# PSFB_low_voltage_supply.net
KiCad netlist of a schematic drawn in Altium Designer
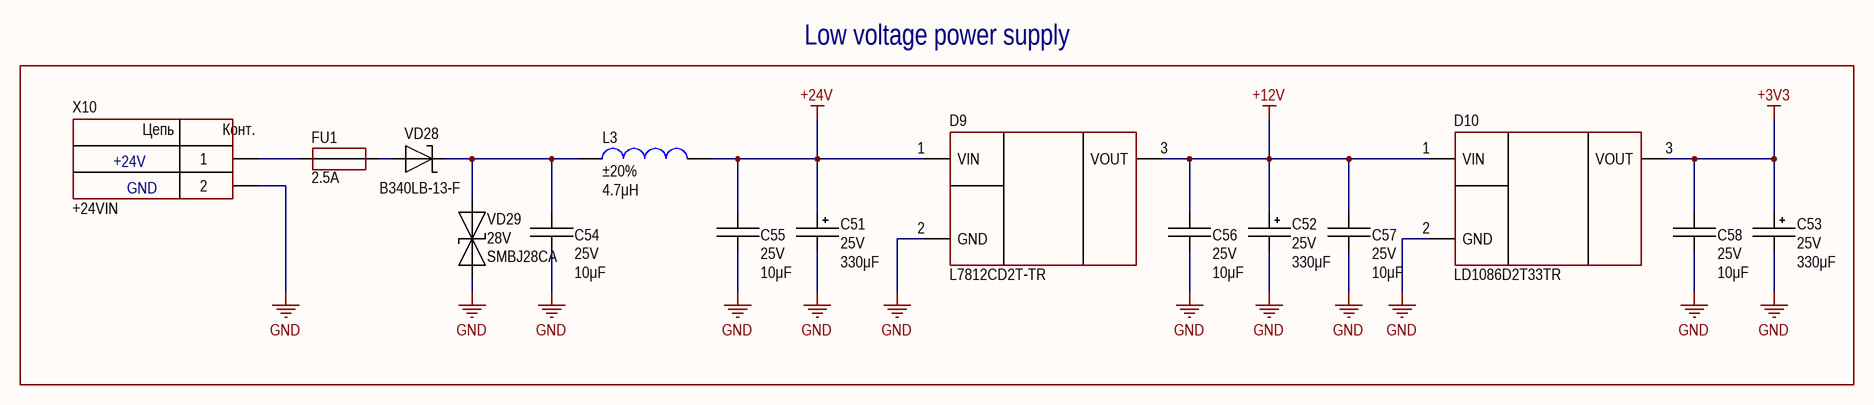
[diagram p0: PSFB_low_voltage_supply.SchDoc]

(export (version "E")
  (design (tool "Eeschema 10.0.6"))
  (components
    (comp (ref "C51")
      (value "330μF")
      (footprint "CAP: D8C3.5H12")
      (description "330µF 25V Aluminum - Polymer Capacitors Radial, Can 18mOhm 2000 Hrs @ 105°C")
      (fields
        (field (name "MANUFACTURER") "KEMET")
        (field (name "PARTNUMBER") "A750KS337M1EAAE018")
        (field (name "VOLTAGE") "25V")
      )
      (libsource (lib "capacitor") (part "Aluminium"))
    )
    (comp (ref "C52")
      (value "330μF")
      (footprint "CAP: D8C3.5H12")
      (description "330µF 25V Aluminum - Polymer Capacitors Radial, Can 18mOhm 2000 Hrs @ 105°C")
      (fields
        (field (name "MANUFACTURER") "KEMET")
        (field (name "PARTNUMBER") "A750KS337M1EAAE018")
        (field (name "VOLTAGE") "25V")
      )
      (libsource (lib "capacitor") (part "Aluminium"))
    )
    (comp (ref "C53")
      (value "330μF")
      (footprint "CAP: D8C3.5H12")
      (description "330µF 25V Aluminum - Polymer Capacitors Radial, Can 18mOhm 2000 Hrs @ 105°C")
      (fields
        (field (name "MANUFACTURER") "KEMET")
        (field (name "PARTNUMBER") "A750KS337M1EAAE018")
        (field (name "VOLTAGE") "25V")
      )
      (libsource (lib "capacitor") (part "Aluminium"))
    )
    (comp (ref "C54")
      (value "10μF")
      (footprint "CAP: 1206")
      (description "10µF ±10% 25V Ceramic Capacitor X7R 1206 (3216 Metric)")
      (fields
        (field (name "MANUFACTURER") "Yageo")
        (field (name "PARTNUMBER") "CC1206KKX7R8BB106")
        (field (name "VOLTAGE") "25V")
      )
      (libsource (lib "capacitor") (part "Ceramic_1206"))
    )
    (comp (ref "C55")
      (value "10μF")
      (footprint "CAP: 1206")
      (description "10µF ±10% 25V Ceramic Capacitor X7R 1206 (3216 Metric)")
      (fields
        (field (name "MANUFACTURER") "Yageo")
        (field (name "PARTNUMBER") "CC1206KKX7R8BB106")
        (field (name "VOLTAGE") "25V")
      )
      (libsource (lib "capacitor") (part "Ceramic_1206"))
    )
    (comp (ref "C56")
      (value "10μF")
      (footprint "CAP: 1206")
      (description "10µF ±10% 25V Ceramic Capacitor X7R 1206 (3216 Metric)")
      (fields
        (field (name "MANUFACTURER") "Yageo")
        (field (name "PARTNUMBER") "CC1206KKX7R8BB106")
        (field (name "VOLTAGE") "25V")
      )
      (libsource (lib "capacitor") (part "Ceramic_1206"))
    )
    (comp (ref "C57")
      (value "10μF")
      (footprint "CAP: 1206")
      (description "10µF ±10% 25V Ceramic Capacitor X7R 1206 (3216 Metric)")
      (fields
        (field (name "MANUFACTURER") "Yageo")
        (field (name "PARTNUMBER") "CC1206KKX7R8BB106")
        (field (name "VOLTAGE") "25V")
      )
      (libsource (lib "capacitor") (part "Ceramic_1206"))
    )
    (comp (ref "C58")
      (value "10μF")
      (footprint "CAP: 1206")
      (description "10µF ±10% 25V Ceramic Capacitor X7R 1206 (3216 Metric)")
      (fields
        (field (name "MANUFACTURER") "Yageo")
        (field (name "PARTNUMBER") "CC1206KKX7R8BB106")
        (field (name "VOLTAGE") "25V")
      )
      (libsource (lib "capacitor") (part "Ceramic_1206"))
    )
    (comp (ref "D9")
      (value "~")
      (footprint "D2PAK")
      (description "Linear Voltage Regulator IC Positive Fixed 1 Output  1.5A D2PAK")
      (fields
        (field (name "MANUFACTURER") "STMicroelectronics")
        (field (name "VALUEMANUFACTURERPARTNUMBER") "Linear voltage regulator, input 14...35V, 2V, output 12V, 1.5A, -40...+125°C, TO-220")
        (field (name "PARTNUMBER") "L7812CD2T-TR")
      )
      (libsource (lib "MyLib") (part "L7805ABV"))
    )
    (comp (ref "D10")
      (value "~")
      (footprint "D2PAK")
      (description "Linear Voltage Regulator IC Positive Fixed 1 Output  1.5A D2PAK")
      (fields
        (field (name "MANUFACTURER") "STMicroelectronics")
        (field (name "VALUEMANUFACTURERPARTNUMBER") "Linear voltage regulator, input 4.8...30V, 2V, output 3.3V, 1.5A, -40...+125°C, TO-220")
        (field (name "PARTNUMBER") "LD1086D2T33TR")
      )
      (libsource (lib "MyLib") (part "L7805ABV"))
    )
    (comp (ref "FU1")
      (value "~")
      (footprint "FUSE: 1206")
      (description "2.5A 125V AC 63V DC Fuse Board Mount (Cartridge Style Excluded) Surface Mount 1206 (3216 Metric)")
      (fields
        (field (name "MANUFACTURER") "Bel Fuse Inc.")
        (field (name "VALUEMANUFACTURERPARTNUMBER") "Electromechanics relay, 63V, 2.5A, 1206, ")
        (field (name "MAXCURRENT") "2.5A")
      )
      (libsource (lib "electromechanics") (part "Fuse"))
    )
    (comp (ref "L3")
      (value "4.7μH")
      (footprint "IND: SDR0403")
      (description "4.7µH Unshielded Wirewound Inductor 1.7A 94mOhm Max Nonstandard")
      (fields
        (field (name "MANUFACTURER") "Bourns")
        (field (name "PARTNUMBER") "SDR0403-4R7ML")
        (field (name "TOLERANCE") "±20%")
      )
      (libsource (lib "inductor") (part "Inductor_SDR0403"))
    )
    (comp (ref "VD28")
      (value "~")
      (footprint "DIODE: SMB")
      (description "Diode Schottky 40V 3A Surface Mount SMB")
      (fields
        (field (name "MANUFACTURER") "Diodes Incorporated")
        (field (name "VALUEMANUFACTURERPARTNUMBER") "Schottky diode, 40V, 3A, 0.45V, 100pF, SMB, -55...+150°C")
        (field (name "PARTNUMBER") "B340LB-13-F")
      )
      (libsource (lib "diode") (part "Schottky_single"))
    )
    (comp (ref "VD29")
      (value "~")
      (footprint "DIODE: SMB")
      (description "45.4V Clamp 13.3A Ipp Tvs Diode Surface Mount DO-214AA (SMBJ)")
      (fields
        (field (name "MANUFACTURER") "Diodes Incorporated")
        (field (name "VALUEMANUFACTURERPARTNUMBER") "TVS diode, 28V, 600W, , , SMB, -55...+150°C")
        (field (name "VOLTAGE") "28V")
        (field (name "PARTNUMBER") "SMBJ28CA")
      )
      (libsource (lib "diode") (part "TVS_single"))
    )
    (comp (ref "X10")
      (value "~")
      (footprint "CON: 6PCV-02-006")
      (description "2 Circuit 0.375\" (9.53mm) Barrier Block Connector, Screws")
      (fields
        (field (name "MANUFACTURER") "TE Connectivity")
        (field (name "VALUEMANUFACTURERPARTNUMBER") "Connector, 2pin, 9.53mm, 300VAC, 25A")
        (field (name "COMMENTTEXT") "+24VIN")
      )
      (libsource (lib "connector") (part "Connector_6PCV-02"))
    )
  )
  (nets
    (net (code "1") (name "+3V3") (class "Default")
      (node (ref "C53") (pin "1") (pinfunction "1_1") (pintype "passive"))
      (node (ref "C58") (pin "1") (pinfunction "1_1") (pintype "passive"))
      (node (ref "D10") (pin "3") (pinfunction "VOUT_3") (pintype "power_in"))
    )
    (net (code "2") (name "+12V") (class "Default")
      (node (ref "C52") (pin "1") (pinfunction "1_1") (pintype "passive"))
      (node (ref "C56") (pin "1") (pinfunction "1_1") (pintype "passive"))
      (node (ref "C57") (pin "1") (pinfunction "1_1") (pintype "passive"))
      (node (ref "D10") (pin "1") (pinfunction "VIN_1") (pintype "power_in"))
      (node (ref "D9") (pin "3") (pinfunction "VOUT_3") (pintype "power_in"))
    )
    (net (code "3") (name "+24V") (class "Default")
      (node (ref "C51") (pin "1") (pinfunction "1_1") (pintype "passive"))
      (node (ref "C55") (pin "1") (pinfunction "1_1") (pintype "passive"))
      (node (ref "D9") (pin "1") (pinfunction "VIN_1") (pintype "power_in"))
      (node (ref "L3") (pin "1") (pinfunction "1_1") (pintype "passive"))
    )
    (net (code "4") (name "GND") (class "Default")
      (node (ref "C51") (pin "2") (pinfunction "2_2") (pintype "passive"))
      (node (ref "C52") (pin "2") (pinfunction "2_2") (pintype "passive"))
      (node (ref "C53") (pin "2") (pinfunction "2_2") (pintype "passive"))
      (node (ref "C54") (pin "2") (pinfunction "2_2") (pintype "passive"))
      (node (ref "C55") (pin "2") (pinfunction "2_2") (pintype "passive"))
      (node (ref "C56") (pin "2") (pinfunction "2_2") (pintype "passive"))
      (node (ref "C57") (pin "2") (pinfunction "2_2") (pintype "passive"))
      (node (ref "C58") (pin "2") (pinfunction "2_2") (pintype "passive"))
      (node (ref "D10") (pin "2") (pinfunction "GND_2") (pintype "power_in"))
      (node (ref "D9") (pin "2") (pinfunction "GND_2") (pintype "power_in"))
      (node (ref "VD29") (pin "2") (pinfunction "C_2") (pintype "passive"))
      (node (ref "X10") (pin "2") (pinfunction "2_2") (pintype "passive"))
    )
    (net (code "5") (name "Net-(FU1-Pad1)") (class "Default")
      (node (ref "FU1") (pin "1") (pinfunction "1_1") (pintype "passive"))
      (node (ref "X10") (pin "1") (pinfunction "1_1") (pintype "passive"))
    )
    (net (code "6") (name "Net-(FU1-Pad2)") (class "Default")
      (node (ref "FU1") (pin "2") (pinfunction "2_2") (pintype "passive"))
      (node (ref "VD28") (pin "1") (pinfunction "1_1") (pintype "passive"))
    )
    (net (code "7") (name "Net-(VD29-A)") (class "Default")
      (node (ref "C54") (pin "1") (pinfunction "1_1") (pintype "passive"))
      (node (ref "L3") (pin "2") (pinfunction "2_2") (pintype "passive"))
      (node (ref "VD28") (pin "2") (pinfunction "2_2") (pintype "passive"))
      (node (ref "VD29") (pin "1") (pinfunction "A_1") (pintype "passive"))
    )
  )
)
